# QCW_GDT_PCB.net
KiCad netlist of a schematic drawn in Altium Designer
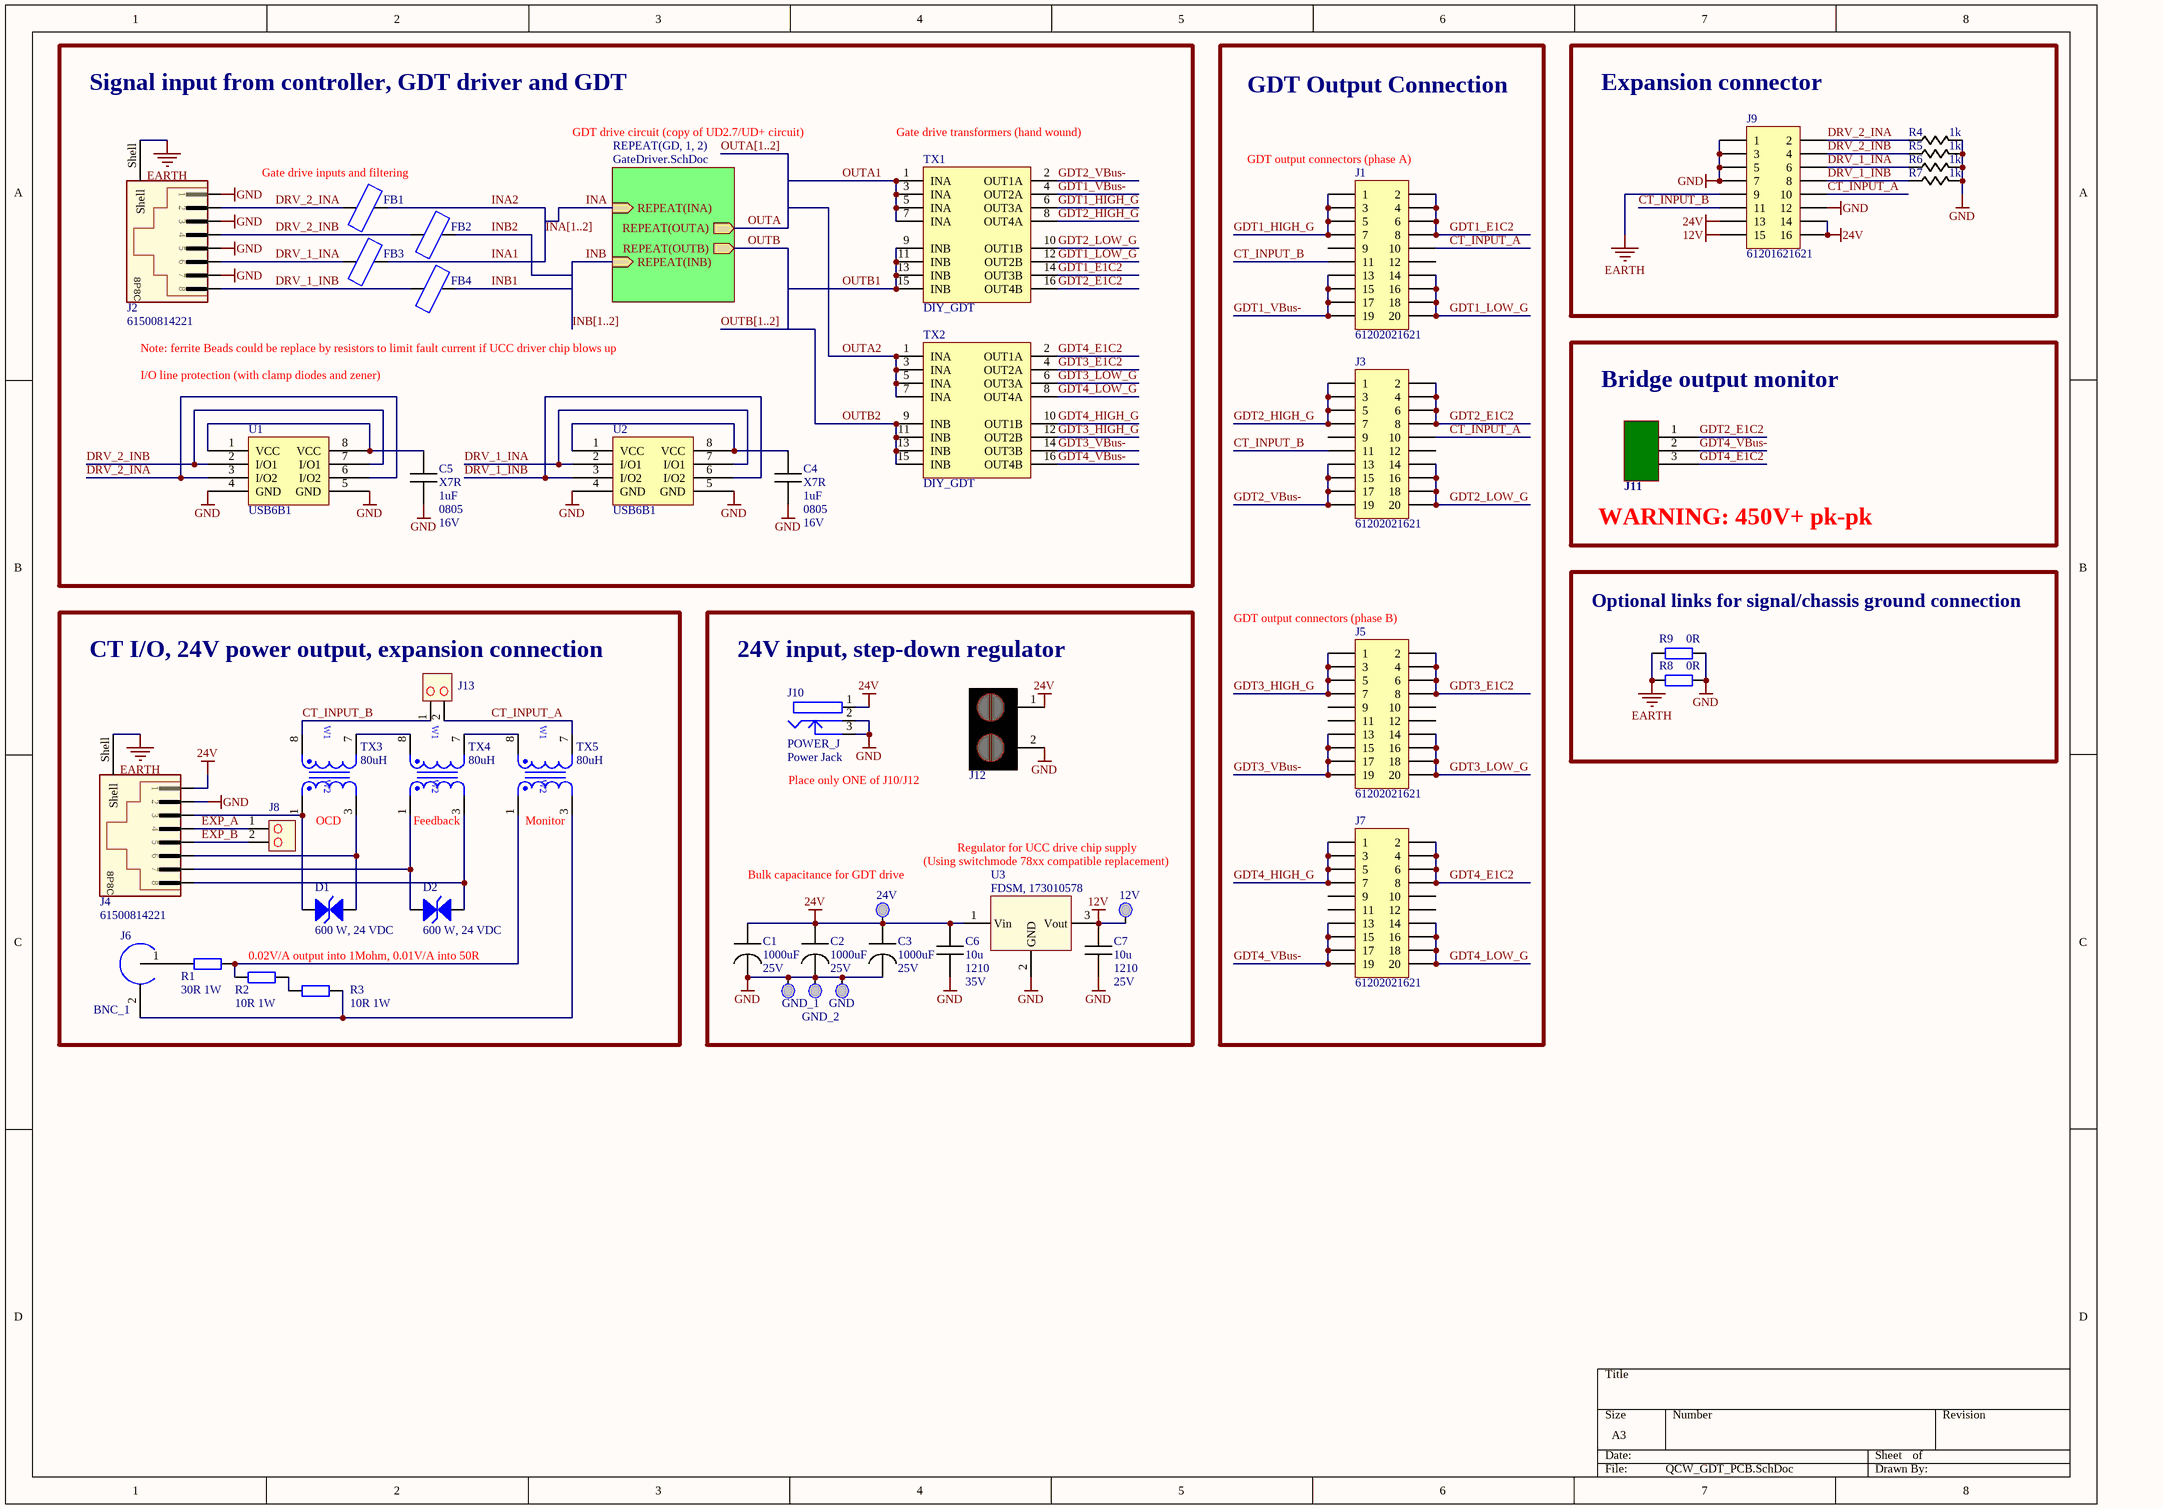
[diagram p0: QCW_GDT_PCB.SchDoc]

(export (version "E")
  (design (tool "Eeschema 10.0.6"))
  (components
    (comp (ref "12V")
      (value "Testpoint")
      (footprint "Keystone5004")
      (libsource (lib "TV_Altium_library") (part "Testpoint"))
    )
    (comp (ref "24V")
      (value "Testpoint")
      (footprint "Keystone5000")
      (libsource (lib "TV_Altium_library") (part "Testpoint"))
    )
    (comp (ref "C1")
      (value "EEU-FM1E102")
      (footprint "12.5mm lytic")
      (description "CAP ALUM 1000UF 20% 25V RADIAL")
      (fields
        (field (name "CAPACITANCE") "1000uF")
        (field (name "VOLTAGE") "25V")
        (field (name "MOUSER PART") "667-EEU-FM1E102")
        (field (name "DIGIKEY PART") "P12379-ND")
      )
      (libsource (lib "TV_Altium_library") (part "electrolytic capacitor"))
    )
    (comp (ref "C2")
      (value "EEU-FM1E102")
      (footprint "12.5mm lytic")
      (description "CAP ALUM 1000UF 20% 25V RADIAL")
      (fields
        (field (name "CAPACITANCE") "1000uF")
        (field (name "VOLTAGE") "25V")
        (field (name "MOUSER PART") "667-EEU-FM1E102")
        (field (name "DIGIKEY PART") "P12379-ND")
      )
      (libsource (lib "TV_Altium_library") (part "electrolytic capacitor"))
    )
    (comp (ref "C3")
      (value "EEU-FM1E102")
      (footprint "12.5mm lytic")
      (description "CAP ALUM 1000UF 20% 25V RADIAL")
      (fields
        (field (name "CAPACITANCE") "1000uF")
        (field (name "VOLTAGE") "25V")
        (field (name "MOUSER PART") "667-EEU-FM1E102")
        (field (name "DIGIKEY PART") "P12379-ND")
      )
      (libsource (lib "TV_Altium_library") (part "electrolytic capacitor"))
    )
    (comp (ref "C4")
      (value "CC0805KKX7R7BB105")
      (footprint "0805C")
      (description "CAP CER 1UF 16V X7R 0805")
      (fields
        (field (name "TOLERANCE") "10%")
        (field (name "MATERIAL") "X7R")
        (field (name "CAPACITANCE") "1uF")
        (field (name "PACKAGE") "0805")
        (field (name "VOLTAGE") "16V")
        (field (name "MOUSER PART") "603-CC805KKX7R7BB105")
      )
      (libsource (lib "UD2 CPLD") (part "Capacitor"))
    )
    (comp (ref "C5")
      (value "CC0805KKX7R7BB105")
      (footprint "0805C")
      (description "CAP CER 1UF 16V X7R 0805")
      (fields
        (field (name "TOLERANCE") "10%")
        (field (name "MATERIAL") "X7R")
        (field (name "CAPACITANCE") "1uF")
        (field (name "PACKAGE") "0805")
        (field (name "VOLTAGE") "16V")
        (field (name "MOUSER PART") "603-CC805KKX7R7BB105")
      )
      (libsource (lib "UD2 CPLD") (part "Capacitor"))
    )
    (comp (ref "C6")
      (value "885012209028")
      (footprint "1210C")
      (fields
        (field (name "CAPACITANCE") "10u")
        (field (name "PACKAGE") "1210")
        (field (name "VOLTAGE") "35V")
      )
      (libsource (lib "TV_Altium_library") (part "Capacitor"))
    )
    (comp (ref "C7")
      (value "885012209028")
      (footprint "1210C")
      (fields
        (field (name "CAPACITANCE") "10u")
        (field (name "PACKAGE") "1210")
        (field (name "VOLTAGE") "25V")
      )
      (libsource (lib "TV_Altium_library") (part "Capacitor"))
    )
    (comp (ref "D1")
      (value "600 W, 24 VDC")
      (footprint "DO-214AA_Bidirectional")
      (description "WE-TVSP Power TVS Diode, bidirectional, 600 W, 24 VDC")
      (fields
        (field (name "PARTNO") "824521241")
        (field (name "MANUFACTURER") "Wurth Elektronik")
        (field (name "CREATED BY") "Baojun Chen")
      )
      (libsource (lib "TV_Altium_library") (part "WE-TVSP DO-214AA, 824521241"))
    )
    (comp (ref "D2")
      (value "600 W, 24 VDC")
      (footprint "DO-214AA_Bidirectional")
      (description "WE-TVSP Power TVS Diode, bidirectional, 600 W, 24 VDC")
      (fields
        (field (name "PARTNO") "824521241")
        (field (name "MANUFACTURER") "Wurth Elektronik")
        (field (name "CREATED BY") "Baojun Chen")
      )
      (libsource (lib "TV_Altium_library") (part "WE-TVSP DO-214AA, 824521241"))
    )
    (comp (ref "FB1")
      (value "FerriteBead")
      (footprint "0805FB")
      (description "Ferrite Bead")
      (libsource (lib "TV_Altium_library") (part "FerriteBead"))
    )
    (comp (ref "FB2")
      (value "FerriteBead")
      (footprint "0805FB")
      (description "Ferrite Bead")
      (libsource (lib "TV_Altium_library") (part "FerriteBead"))
    )
    (comp (ref "FB3")
      (value "FerriteBead")
      (footprint "0805FB")
      (description "Ferrite Bead")
      (libsource (lib "TV_Altium_library") (part "FerriteBead"))
    )
    (comp (ref "FB4")
      (value "FerriteBead")
      (footprint "0805FB")
      (description "Ferrite Bead")
      (libsource (lib "TV_Altium_library") (part "FerriteBead"))
    )
    (comp (ref "GND")
      (value "Testpoint")
      (footprint "Keystone5001")
      (libsource (lib "TV_Altium_library") (part "Testpoint"))
    )
    (comp (ref "GND_1")
      (value "Testpoint")
      (footprint "Keystone5001")
      (libsource (lib "TV_Altium_library") (part "Testpoint"))
    )
    (comp (ref "GND_2")
      (value "Testpoint")
      (footprint "Keystone5001")
      (libsource (lib "TV_Altium_library") (part "Testpoint"))
    )
    (comp (ref "J1")
      (value "61202021621")
      (footprint "61202021621")
      (description "WR-BHD 2.54mm Male Box Header")
      (fields (field (name "MANUFACTURER") "Wurth Elektronik") (field (name "CREATED BY") "Baojun Chen"))
      (libsource (lib "TV_Altium_library") (part "61202021621"))
    )
    (comp (ref "J2")
      (value "61500814221")
      (footprint "61500814221")
      (description "WR-MJ Modular Jack Horizontal Shielded 8P8C Tab Down")
      (fields (field (name "PUBLISHER") "Wurth Elektronik"))
      (libsource (lib "TV_Altium_library") (part "61500814221"))
    )
    (comp (ref "J3")
      (value "61202021621")
      (footprint "61202021621")
      (description "WR-BHD 2.54mm Male Box Header")
      (fields (field (name "MANUFACTURER") "Wurth Elektronik") (field (name "CREATED BY") "Baojun Chen"))
      (libsource (lib "TV_Altium_library") (part "61202021621"))
    )
    (comp (ref "J4")
      (value "61500814221")
      (footprint "61500814221")
      (description "WR-MJ Modular Jack Horizontal Shielded 8P8C Tab Down")
      (fields (field (name "PUBLISHER") "Wurth Elektronik"))
      (libsource (lib "TV_Altium_library") (part "61500814221"))
    )
    (comp (ref "J5")
      (value "61202021621")
      (footprint "61202021621")
      (description "WR-BHD 2.54mm Male Box Header")
      (fields (field (name "MANUFACTURER") "Wurth Elektronik") (field (name "CREATED BY") "Baojun Chen"))
      (libsource (lib "TV_Altium_library") (part "61202021621"))
    )
    (comp (ref "J6")
      (value "BNC_1")
      (footprint "BNC_PLASTIC_ELBOW_SOCKET_WITH_MOUNTING_POSTS")
      (description "BNC Connector")
      (libsource (lib "TV_Altium_library") (part "BNC_1"))
    )
    (comp (ref "J7")
      (value "61202021621")
      (footprint "61202021621")
      (description "WR-BHD 2.54mm Male Box Header")
      (fields (field (name "MANUFACTURER") "Wurth Elektronik") (field (name "CREATED BY") "Baojun Chen"))
      (libsource (lib "TV_Altium_library") (part "61202021621"))
    )
    (comp (ref "J8")
      (value "22-23-2021")
      (footprint "22-23-2021")
      (description "Pin Header, 2 Position, Locking, .1 Centers")
      (libsource (lib "") (part "22-23-2021_1"))
    )
    (comp (ref "J9")
      (value "61201621621")
      (footprint "61201621621")
      (description "WR-BHD 2.54mm Male Box Header")
      (fields (field (name "MANUFACTURER") "Wurth Elektronik") (field (name "CREATED BY") "Baojun Chen"))
      (libsource (lib "TV_Altium_library") (part "61201621621"))
    )
    (comp (ref "J10")
      (value "POWER_J")
      (footprint "TV_Altium_Library:POWER_J_SLOT")
      (description "Low Voltage Power Supply Connector")
      (fields
        (field (name "PART_NUMBER") "OVC-CON-10108")
        (field (name "ALTIUM_VALUE") "Power Jack")
        (field (name "PUBLISHER") "Altium Limited")
      )
      (libsource (lib "TV_Altium_library") (part "POWER_J"))
    )
    (comp (ref "J11")
      (value "Header_3_right_angle_th_3.81mm")
      (footprint "691322310003")
      (description "3-way header")
      (libsource (lib "TV_Altium_library") (part "Header_3_right_angle_th_3.81mm"))
    )
    (comp (ref "J12")
      (value "Header_2_5.08mm_Screw_Black")
      (footprint "1776119-2")
      (description "2-way PCB connector")
      (libsource (lib "TV_Altium_library") (part "Header_2_5.08mm_Screw_Black"))
    )
    (comp (ref "J13")
      (value "22-23-2021")
      (footprint "22-23-2021")
      (description "Pin Header, 2 Position, Locking, .1 Centers")
      (libsource (lib "TV_Altium_library") (part "22-23-2021"))
    )
    (comp (ref "R1")
      (value "30R 1W")
      (footprint "RES_2512")
      (libsource (lib "TV_Altium_library") (part "Resistor"))
    )
    (comp (ref "R2")
      (value "10R 1W")
      (footprint "RES_2512")
      (libsource (lib "TV_Altium_library") (part "Resistor"))
    )
    (comp (ref "R3")
      (value "10R 1W")
      (footprint "RES_2512")
      (libsource (lib "TV_Altium_library") (part "Resistor"))
    )
    (comp (ref "R4")
      (value "RC0805FR-071KL")
      (footprint "0805R")
      (description "RES SMD 1K OHM 1% 1/8W 0805")
      (fields
        (field (name "POWER") "0.125W")
        (field (name "RESISTANCE") "1k")
        (field (name "TOLERANCE") "1%")
      )
      (libsource (lib "UD2 CPLD") (part "Resistor"))
    )
    (comp (ref "R5")
      (value "RC0805FR-071KL")
      (footprint "0805R")
      (description "RES SMD 1K OHM 1% 1/8W 0805")
      (fields
        (field (name "POWER") "0.125W")
        (field (name "RESISTANCE") "1k")
        (field (name "TOLERANCE") "1%")
      )
      (libsource (lib "UD2 CPLD") (part "Resistor"))
    )
    (comp (ref "R6")
      (value "RC0805FR-071KL")
      (footprint "0805R")
      (description "RES SMD 1K OHM 1% 1/8W 0805")
      (fields
        (field (name "POWER") "0.125W")
        (field (name "RESISTANCE") "1k")
        (field (name "TOLERANCE") "1%")
      )
      (libsource (lib "UD2 CPLD") (part "Resistor"))
    )
    (comp (ref "R7")
      (value "RC0805FR-071KL")
      (footprint "0805R")
      (description "RES SMD 1K OHM 1% 1/8W 0805")
      (fields
        (field (name "POWER") "0.125W")
        (field (name "RESISTANCE") "1k")
        (field (name "TOLERANCE") "1%")
      )
      (libsource (lib "UD2 CPLD") (part "Resistor"))
    )
    (comp (ref "R8") (value "0R") (footprint "1206R") (libsource (lib "TV_Altium_library") (part "Resistor")))
    (comp (ref "R9") (value "0R") (footprint "1206R") (libsource (lib "TV_Altium_library") (part "Resistor")))
    (comp (ref "TX1")
      (value "DIY_GDT")
      (footprint "GDT_DIY")
      (description "DIY Gate Drive TX on 36x22x14 toroid")
      (libsource (lib "TV_Altium_library") (part "GDT_DIY"))
    )
    (comp (ref "TX2")
      (value "DIY_GDT")
      (footprint "GDT_DIY")
      (description "DIY Gate Drive TX on 36x22x14 toroid")
      (libsource (lib "TV_Altium_library") (part "GDT_DIY"))
    )
    (comp (ref "TX3")
      (value "80uH")
      (footprint "WE-CST_EE5")
      (description "WE-CST Current Sense Transformer, EE5, 80uH")
      (fields (field (name "PARTNUMBER") "749251020") (field (name "PUBLISHER") "Wurth Elektronik"))
      (libsource (lib "TV_Altium_library") (part "WE-CST, 749251020"))
    )
    (comp (ref "TX4")
      (value "80uH")
      (footprint "WE-CST_EE5")
      (description "WE-CST Current Sense Transformer, EE5, 80uH")
      (fields (field (name "PARTNUMBER") "749251020") (field (name "PUBLISHER") "Wurth Elektronik"))
      (libsource (lib "TV_Altium_library") (part "WE-CST, 749251020"))
    )
    (comp (ref "TX5")
      (value "80uH")
      (footprint "WE-CST_EE5")
      (description "WE-CST Current Sense Transformer, EE5, 80uH")
      (fields (field (name "PARTNUMBER") "749251020") (field (name "PUBLISHER") "Wurth Elektronik"))
      (libsource (lib "TV_Altium_library") (part "WE-CST, 749251020"))
    )
    (comp (ref "U1")
      (value "USB6B1")
      (footprint "SOIC-8")
      (description "USB Data Line Protection")
      (libsource (lib "TV_Altium_library") (part "USB6B1"))
    )
    (comp (ref "U2")
      (value "USB6B1")
      (footprint "SOIC-8")
      (description "USB Data Line Protection")
      (libsource (lib "TV_Altium_library") (part "USB6B1"))
    )
    (comp (ref "U3")
      (value "FDSM, 173010578")
      (footprint "WE-FDSM_173010x78")
      (description "MagI³C-FDSM Fixed Step Down Regulator Module")
      (fields (field (name "PARTNUMBER") "173010578") (field (name "PUBLISHER") "Wurth Elektronik"))
      (libsource (lib "TV_Altium_library") (part "FDSM, 173010578"))
    )
  )
  (nets
    (net (code "1") (name "/CT_INPUT_A") (class "Default")
      (node (ref "J1") (pin "10") (pinfunction "10_10") (pintype "passive"))
      (node (ref "J13") (pin "2") (pinfunction "2_2") (pintype "passive"))
      (node (ref "J3") (pin "10") (pinfunction "10_10") (pintype "passive"))
      (node (ref "J9") (pin "10") (pinfunction "10_10") (pintype "passive"))
      (node (ref "TX5") (pin "7") (pinfunction "7_7") (pintype "passive"))
    )
    (net (code "2") (name "/CT_INPUT_B") (class "Default")
      (node (ref "J1") (pin "11") (pinfunction "11_11") (pintype "passive"))
      (node (ref "J13") (pin "1") (pinfunction "1_1") (pintype "passive"))
      (node (ref "J3") (pin "11") (pinfunction "11_11") (pintype "passive"))
      (node (ref "J9") (pin "11") (pinfunction "11_11") (pintype "passive"))
      (node (ref "TX3") (pin "8") (pinfunction "8_8") (pintype "passive"))
    )
    (net (code "3") (name "/DRV_1_INA") (class "Default")
      (node (ref "FB3") (pin "1") (pinfunction "1_1") (pintype "passive"))
      (node (ref "J2") (pin "6") (pinfunction "6_6") (pintype "passive"))
      (node (ref "J9") (pin "6") (pinfunction "6_6") (pintype "passive"))
      (node (ref "R6") (pin "2") (pinfunction "2_2") (pintype "passive"))
      (node (ref "U2") (pin "2") (pinfunction "I/O1_2") (pintype "passive"))
      (node (ref "U2") (pin "7") (pinfunction "I/O1_7") (pintype "passive"))
    )
    (net (code "4") (name "/DRV_1_INB") (class "Default")
      (node (ref "FB4") (pin "1") (pinfunction "1_1") (pintype "passive"))
      (node (ref "J2") (pin "8") (pinfunction "8_8") (pintype "passive"))
      (node (ref "J9") (pin "8") (pinfunction "8_8") (pintype "passive"))
      (node (ref "R7") (pin "2") (pinfunction "2_2") (pintype "passive"))
      (node (ref "U2") (pin "3") (pinfunction "I/O2_3") (pintype "passive"))
      (node (ref "U2") (pin "6") (pinfunction "I/O2_6") (pintype "passive"))
    )
    (net (code "5") (name "/DRV_2_INA") (class "Default")
      (node (ref "FB1") (pin "1") (pinfunction "1_1") (pintype "passive"))
      (node (ref "J2") (pin "2") (pinfunction "2_2") (pintype "passive"))
      (node (ref "J9") (pin "2") (pinfunction "2_2") (pintype "passive"))
      (node (ref "R4") (pin "2") (pinfunction "2_2") (pintype "passive"))
      (node (ref "U1") (pin "3") (pinfunction "I/O2_3") (pintype "passive"))
      (node (ref "U1") (pin "6") (pinfunction "I/O2_6") (pintype "passive"))
    )
    (net (code "6") (name "/DRV_2_INB") (class "Default")
      (node (ref "FB2") (pin "1") (pinfunction "1_1") (pintype "passive"))
      (node (ref "J2") (pin "4") (pinfunction "4_4") (pintype "passive"))
      (node (ref "J9") (pin "4") (pinfunction "4_4") (pintype "passive"))
      (node (ref "R5") (pin "2") (pinfunction "2_2") (pintype "passive"))
      (node (ref "U1") (pin "2") (pinfunction "I/O1_2") (pintype "passive"))
      (node (ref "U1") (pin "7") (pinfunction "I/O1_7") (pintype "passive"))
    )
    (net (code "7") (name "/EXP_A") (class "Default")
      (node (ref "J4") (pin "4") (pinfunction "4_4") (pintype "passive"))
      (node (ref "J8") (pin "1") (pinfunction "1_1") (pintype "passive"))
    )
    (net (code "8") (name "/EXP_B") (class "Default")
      (node (ref "J4") (pin "5") (pinfunction "5_5") (pintype "passive"))
      (node (ref "J8") (pin "2") (pinfunction "2_2") (pintype "passive"))
    )
    (net (code "9") (name "/GDT1_E1C2") (class "Default")
      (node (ref "J1") (pin "2") (pinfunction "2_2") (pintype "passive"))
      (node (ref "J1") (pin "4") (pinfunction "4_4") (pintype "passive"))
      (node (ref "J1") (pin "6") (pinfunction "6_6") (pintype "passive"))
      (node (ref "J1") (pin "8") (pinfunction "8_8") (pintype "passive"))
      (node (ref "TX1") (pin "14") (pinfunction "OUT3B_14") (pintype "passive"))
    )
    (net (code "10") (name "/GDT1_HIGH_G") (class "Default")
      (node (ref "J1") (pin "1") (pinfunction "1_1") (pintype "passive"))
      (node (ref "J1") (pin "3") (pinfunction "3_3") (pintype "passive"))
      (node (ref "J1") (pin "5") (pinfunction "5_5") (pintype "passive"))
      (node (ref "J1") (pin "7") (pinfunction "7_7") (pintype "passive"))
      (node (ref "TX1") (pin "6") (pinfunction "OUT3A_6") (pintype "passive"))
    )
    (net (code "11") (name "/GDT1_LOW_G") (class "Default")
      (node (ref "J1") (pin "14") (pinfunction "14_14") (pintype "passive"))
      (node (ref "J1") (pin "16") (pinfunction "16_16") (pintype "passive"))
      (node (ref "J1") (pin "18") (pinfunction "18_18") (pintype "passive"))
      (node (ref "J1") (pin "20") (pinfunction "20_20") (pintype "passive"))
      (node (ref "TX1") (pin "12") (pinfunction "OUT2B_12") (pintype "passive"))
    )
    (net (code "12") (name "/GDT1_VBus-") (class "Default")
      (node (ref "J1") (pin "13") (pinfunction "13_13") (pintype "passive"))
      (node (ref "J1") (pin "15") (pinfunction "15_15") (pintype "passive"))
      (node (ref "J1") (pin "17") (pinfunction "17_17") (pintype "passive"))
      (node (ref "J1") (pin "19") (pinfunction "19_19") (pintype "passive"))
      (node (ref "TX1") (pin "4") (pinfunction "OUT2A_4") (pintype "passive"))
    )
    (net (code "13") (name "/GDT2_E1C2") (class "Default")
      (node (ref "J11") (pin "1") (pintype "passive"))
      (node (ref "J3") (pin "2") (pinfunction "2_2") (pintype "passive"))
      (node (ref "J3") (pin "4") (pinfunction "4_4") (pintype "passive"))
      (node (ref "J3") (pin "6") (pinfunction "6_6") (pintype "passive"))
      (node (ref "J3") (pin "8") (pinfunction "8_8") (pintype "passive"))
      (node (ref "TX1") (pin "16") (pinfunction "OUT4B_16") (pintype "passive"))
    )
    (net (code "14") (name "/GDT2_HIGH_G") (class "Default")
      (node (ref "J3") (pin "1") (pinfunction "1_1") (pintype "passive"))
      (node (ref "J3") (pin "3") (pinfunction "3_3") (pintype "passive"))
      (node (ref "J3") (pin "5") (pinfunction "5_5") (pintype "passive"))
      (node (ref "J3") (pin "7") (pinfunction "7_7") (pintype "passive"))
      (node (ref "TX1") (pin "8") (pinfunction "OUT4A_8") (pintype "passive"))
    )
    (net (code "15") (name "/GDT2_LOW_G") (class "Default")
      (node (ref "J3") (pin "14") (pinfunction "14_14") (pintype "passive"))
      (node (ref "J3") (pin "16") (pinfunction "16_16") (pintype "passive"))
      (node (ref "J3") (pin "18") (pinfunction "18_18") (pintype "passive"))
      (node (ref "J3") (pin "20") (pinfunction "20_20") (pintype "passive"))
      (node (ref "TX1") (pin "10") (pinfunction "OUT1B_10") (pintype "passive"))
    )
    (net (code "16") (name "/GDT2_VBus-") (class "Default")
      (node (ref "J3") (pin "13") (pinfunction "13_13") (pintype "passive"))
      (node (ref "J3") (pin "15") (pinfunction "15_15") (pintype "passive"))
      (node (ref "J3") (pin "17") (pinfunction "17_17") (pintype "passive"))
      (node (ref "J3") (pin "19") (pinfunction "19_19") (pintype "passive"))
      (node (ref "TX1") (pin "2") (pinfunction "OUT1A_2") (pintype "passive"))
    )
    (net (code "17") (name "/GDT3_E1C2") (class "Default")
      (node (ref "J5") (pin "2") (pinfunction "2_2") (pintype "passive"))
      (node (ref "J5") (pin "4") (pinfunction "4_4") (pintype "passive"))
      (node (ref "J5") (pin "6") (pinfunction "6_6") (pintype "passive"))
      (node (ref "J5") (pin "8") (pinfunction "8_8") (pintype "passive"))
      (node (ref "TX2") (pin "4") (pinfunction "OUT2A_4") (pintype "passive"))
    )
    (net (code "18") (name "/GDT3_HIGH_G") (class "Default")
      (node (ref "J5") (pin "1") (pinfunction "1_1") (pintype "passive"))
      (node (ref "J5") (pin "3") (pinfunction "3_3") (pintype "passive"))
      (node (ref "J5") (pin "5") (pinfunction "5_5") (pintype "passive"))
      (node (ref "J5") (pin "7") (pinfunction "7_7") (pintype "passive"))
      (node (ref "TX2") (pin "12") (pinfunction "OUT2B_12") (pintype "passive"))
    )
    (net (code "19") (name "/GDT3_LOW_G") (class "Default")
      (node (ref "J5") (pin "14") (pinfunction "14_14") (pintype "passive"))
      (node (ref "J5") (pin "16") (pinfunction "16_16") (pintype "passive"))
      (node (ref "J5") (pin "18") (pinfunction "18_18") (pintype "passive"))
      (node (ref "J5") (pin "20") (pinfunction "20_20") (pintype "passive"))
      (node (ref "TX2") (pin "6") (pinfunction "OUT3A_6") (pintype "passive"))
    )
    (net (code "20") (name "/GDT3_VBus-") (class "Default")
      (node (ref "J5") (pin "13") (pinfunction "13_13") (pintype "passive"))
      (node (ref "J5") (pin "15") (pinfunction "15_15") (pintype "passive"))
      (node (ref "J5") (pin "17") (pinfunction "17_17") (pintype "passive"))
      (node (ref "J5") (pin "19") (pinfunction "19_19") (pintype "passive"))
      (node (ref "TX2") (pin "14") (pinfunction "OUT3B_14") (pintype "passive"))
    )
    (net (code "21") (name "/GDT4_E1C2") (class "Default")
      (node (ref "J11") (pin "3") (pintype "passive"))
      (node (ref "J7") (pin "2") (pinfunction "2_2") (pintype "passive"))
      (node (ref "J7") (pin "4") (pinfunction "4_4") (pintype "passive"))
      (node (ref "J7") (pin "6") (pinfunction "6_6") (pintype "passive"))
      (node (ref "J7") (pin "8") (pinfunction "8_8") (pintype "passive"))
      (node (ref "TX2") (pin "2") (pinfunction "OUT1A_2") (pintype "passive"))
    )
    (net (code "22") (name "/GDT4_HIGH_G") (class "Default")
      (node (ref "J7") (pin "1") (pinfunction "1_1") (pintype "passive"))
      (node (ref "J7") (pin "3") (pinfunction "3_3") (pintype "passive"))
      (node (ref "J7") (pin "5") (pinfunction "5_5") (pintype "passive"))
      (node (ref "J7") (pin "7") (pinfunction "7_7") (pintype "passive"))
      (node (ref "TX2") (pin "10") (pinfunction "OUT1B_10") (pintype "passive"))
    )
    (net (code "23") (name "/GDT4_LOW_G") (class "Default")
      (node (ref "J7") (pin "14") (pinfunction "14_14") (pintype "passive"))
      (node (ref "J7") (pin "16") (pinfunction "16_16") (pintype "passive"))
      (node (ref "J7") (pin "18") (pinfunction "18_18") (pintype "passive"))
      (node (ref "J7") (pin "20") (pinfunction "20_20") (pintype "passive"))
      (node (ref "TX2") (pin "8") (pinfunction "OUT4A_8") (pintype "passive"))
    )
    (net (code "24") (name "/GDT4_VBus-") (class "Default")
      (node (ref "J11") (pin "2") (pintype "passive"))
      (node (ref "J7") (pin "13") (pinfunction "13_13") (pintype "passive"))
      (node (ref "J7") (pin "15") (pinfunction "15_15") (pintype "passive"))
      (node (ref "J7") (pin "17") (pinfunction "17_17") (pintype "passive"))
      (node (ref "J7") (pin "19") (pinfunction "19_19") (pintype "passive"))
      (node (ref "TX2") (pin "16") (pinfunction "OUT4B_16") (pintype "passive"))
    )
    (net (code "26") (name "/INA1") (class "Default")
      (node (ref "FB3") (pin "2") (pinfunction "2_2") (pintype "passive"))
    )
    (net (code "27") (name "/INA2") (class "Default")
      (node (ref "FB1") (pin "2") (pinfunction "2_2") (pintype "passive"))
    )
    (net (code "30") (name "/INB1") (class "Default")
      (node (ref "FB4") (pin "2") (pinfunction "2_2") (pintype "passive"))
    )
    (net (code "31") (name "/INB2") (class "Default")
      (node (ref "FB2") (pin "2") (pinfunction "2_2") (pintype "passive"))
    )
    (net (code "34") (name "/OUTA1") (class "Default")
      (node (ref "TX1") (pin "1") (pinfunction "INA_1") (pintype "passive"))
      (node (ref "TX1") (pin "3") (pinfunction "INA_3") (pintype "passive"))
      (node (ref "TX1") (pin "5") (pinfunction "INA_5") (pintype "passive"))
      (node (ref "TX1") (pin "7") (pinfunction "INA_7") (pintype "passive"))
    )
    (net (code "35") (name "/OUTA2") (class "Default")
      (node (ref "TX2") (pin "1") (pinfunction "INA_1") (pintype "passive"))
      (node (ref "TX2") (pin "3") (pinfunction "INA_3") (pintype "passive"))
      (node (ref "TX2") (pin "5") (pinfunction "INA_5") (pintype "passive"))
      (node (ref "TX2") (pin "7") (pinfunction "INA_7") (pintype "passive"))
    )
    (net (code "38") (name "/OUTB1") (class "Default")
      (node (ref "TX1") (pin "11") (pinfunction "INB_11") (pintype "passive"))
      (node (ref "TX1") (pin "13") (pinfunction "INB_13") (pintype "passive"))
      (node (ref "TX1") (pin "15") (pinfunction "INB_15") (pintype "passive"))
      (node (ref "TX1") (pin "9") (pinfunction "INB_9") (pintype "passive"))
    )
    (net (code "39") (name "/OUTB2") (class "Default")
      (node (ref "TX2") (pin "11") (pinfunction "INB_11") (pintype "passive"))
      (node (ref "TX2") (pin "13") (pinfunction "INB_13") (pintype "passive"))
      (node (ref "TX2") (pin "15") (pinfunction "INB_15") (pintype "passive"))
      (node (ref "TX2") (pin "9") (pinfunction "INB_9") (pintype "passive"))
    )
    (net (code "41") (name "12V") (class "Default")
      (node (ref "12V") (pin "1") (pinfunction "1_1") (pintype "passive"))
      (node (ref "C7") (pin "1") (pinfunction "1_1") (pintype "passive"))
      (node (ref "J9") (pin "15") (pinfunction "15_15") (pintype "passive"))
      (node (ref "U3") (pin "3") (pinfunction "Vout_3") (pintype "passive"))
    )
    (net (code "42") (name "24V") (class "Default")
      (node (ref "24V") (pin "1") (pinfunction "1_1") (pintype "passive"))
      (node (ref "C1") (pin "1") (pinfunction "1_1") (pintype "passive"))
      (node (ref "C2") (pin "1") (pinfunction "1_1") (pintype "passive"))
      (node (ref "C3") (pin "1") (pinfunction "1_1") (pintype "passive"))
      (node (ref "C6") (pin "1") (pinfunction "1_1") (pintype "passive"))
      (node (ref "J10") (pin "1") (pinfunction "1_1") (pintype "power_in"))
      (node (ref "J12") (pin "1") (pinfunction "1_1") (pintype "passive"))
      (node (ref "J4") (pin "1") (pinfunction "1_1") (pintype "passive"))
      (node (ref "J9") (pin "13") (pinfunction "13_13") (pintype "passive"))
      (node (ref "J9") (pin "14") (pinfunction "14_14") (pintype "passive"))
      (node (ref "J9") (pin "16") (pinfunction "16_16") (pintype "passive"))
      (node (ref "U3") (pin "1") (pinfunction "Vin_1") (pintype "passive"))
    )
    (net (code "43") (name "EARTH") (class "Default")
      (node (ref "J2") (pin "Shell") (pinfunction "Shell_Shell") (pintype "passive"))
      (node (ref "J4") (pin "Shell") (pinfunction "Shell_Shell") (pintype "passive"))
      (node (ref "J9") (pin "9") (pinfunction "9_9") (pintype "passive"))
      (node (ref "R8") (pin "2") (pinfunction "2_2") (pintype "passive"))
      (node (ref "R9") (pin "2") (pinfunction "2_2") (pintype "passive"))
    )
    (net (code "44") (name "GND") (class "Default")
      (node (ref "C1") (pin "2") (pinfunction "2_2") (pintype "passive"))
      (node (ref "C2") (pin "2") (pinfunction "2_2") (pintype "passive"))
      (node (ref "C3") (pin "2") (pinfunction "2_2") (pintype "passive"))
      (node (ref "C4") (pin "1") (pinfunction "1_1") (pintype "passive"))
      (node (ref "C5") (pin "1") (pinfunction "1_1") (pintype "passive"))
      (node (ref "C6") (pin "2") (pinfunction "2_2") (pintype "passive"))
      (node (ref "C7") (pin "2") (pinfunction "2_2") (pintype "passive"))
      (node (ref "GND") (pin "1") (pinfunction "1_1") (pintype "passive"))
      (node (ref "GND_1") (pin "1") (pinfunction "1_1") (pintype "passive"))
      (node (ref "GND_2") (pin "1") (pinfunction "1_1") (pintype "passive"))
      (node (ref "J10") (pin "2") (pinfunction "2_2") (pintype "power_in"))
      (node (ref "J10") (pin "3") (pinfunction "3_3") (pintype "power_in"))
      (node (ref "J12") (pin "2") (pinfunction "2_2") (pintype "passive"))
      (node (ref "J2") (pin "1") (pinfunction "1_1") (pintype "passive"))
      (node (ref "J2") (pin "3") (pinfunction "3_3") (pintype "passive"))
      (node (ref "J2") (pin "5") (pinfunction "5_5") (pintype "passive"))
      (node (ref "J2") (pin "7") (pinfunction "7_7") (pintype "passive"))
      (node (ref "J4") (pin "2") (pinfunction "2_2") (pintype "passive"))
      (node (ref "J9") (pin "1") (pinfunction "1_1") (pintype "passive"))
      (node (ref "J9") (pin "12") (pinfunction "12_12") (pintype "passive"))
      (node (ref "J9") (pin "3") (pinfunction "3_3") (pintype "passive"))
      (node (ref "J9") (pin "5") (pinfunction "5_5") (pintype "passive"))
      (node (ref "J9") (pin "7") (pinfunction "7_7") (pintype "passive"))
      (node (ref "R4") (pin "1") (pinfunction "1_1") (pintype "passive"))
      (node (ref "R5") (pin "1") (pinfunction "1_1") (pintype "passive"))
      (node (ref "R6") (pin "1") (pinfunction "1_1") (pintype "passive"))
      (node (ref "R7") (pin "1") (pinfunction "1_1") (pintype "passive"))
      (node (ref "R8") (pin "1") (pinfunction "1_1") (pintype "passive"))
      (node (ref "R9") (pin "1") (pinfunction "1_1") (pintype "passive"))
      (node (ref "U1") (pin "4") (pinfunction "GND_4") (pintype "passive"))
      (node (ref "U1") (pin "5") (pinfunction "GND_5") (pintype "passive"))
      (node (ref "U2") (pin "4") (pinfunction "GND_4") (pintype "passive"))
      (node (ref "U2") (pin "5") (pinfunction "GND_5") (pintype "passive"))
      (node (ref "U3") (pin "2") (pinfunction "GND_2") (pintype "passive"))
    )
    (net (code "45") (name "Net-(C4-Pad2)") (class "Default")
      (node (ref "C4") (pin "2") (pinfunction "2_2") (pintype "passive"))
      (node (ref "U2") (pin "1") (pinfunction "VCC_1") (pintype "passive"))
      (node (ref "U2") (pin "8") (pinfunction "VCC_8") (pintype "passive"))
    )
    (net (code "46") (name "Net-(C5-Pad2)") (class "Default")
      (node (ref "C5") (pin "2") (pinfunction "2_2") (pintype "passive"))
      (node (ref "U1") (pin "1") (pinfunction "VCC_1") (pintype "passive"))
      (node (ref "U1") (pin "8") (pinfunction "VCC_8") (pintype "passive"))
    )
    (net (code "47") (name "Net-(D1-Pad1)") (class "Default")
      (node (ref "D1") (pin "1") (pinfunction "1_1") (pintype "passive"))
      (node (ref "J4") (pin "3") (pinfunction "3_3") (pintype "passive"))
      (node (ref "TX3") (pin "1") (pinfunction "1_1") (pintype "passive"))
    )
    (net (code "48") (name "Net-(D1-Pad2)") (class "Default")
      (node (ref "D1") (pin "2") (pinfunction "2_2") (pintype "passive"))
      (node (ref "J4") (pin "6") (pinfunction "6_6") (pintype "passive"))
      (node (ref "TX3") (pin "3") (pinfunction "3_3") (pintype "passive"))
    )
    (net (code "49") (name "Net-(D2-Pad1)") (class "Default")
      (node (ref "D2") (pin "1") (pinfunction "1_1") (pintype "passive"))
      (node (ref "J4") (pin "7") (pinfunction "7_7") (pintype "passive"))
      (node (ref "TX4") (pin "1") (pinfunction "1_1") (pintype "passive"))
    )
    (net (code "50") (name "Net-(D2-Pad2)") (class "Default")
      (node (ref "D2") (pin "2") (pinfunction "2_2") (pintype "passive"))
      (node (ref "J4") (pin "8") (pinfunction "8_8") (pintype "passive"))
      (node (ref "TX4") (pin "3") (pinfunction "3_3") (pintype "passive"))
    )
    (net (code "51") (name "Net-(J6-Centre)") (class "Default")
      (node (ref "J6") (pin "1") (pinfunction "Centre_1") (pintype "passive"))
      (node (ref "R1") (pin "2") (pinfunction "2_2") (pintype "passive"))
    )
    (net (code "52") (name "Net-(J6-Shield)") (class "Default")
      (node (ref "J6") (pin "2") (pinfunction "Shield_2") (pintype "passive"))
      (node (ref "R3") (pin "1") (pinfunction "1_1") (pintype "passive"))
      (node (ref "TX5") (pin "3") (pinfunction "3_3") (pintype "passive"))
    )
    (net (code "53") (name "Net-(R1-Pad1)") (class "Default")
      (node (ref "R1") (pin "1") (pinfunction "1_1") (pintype "passive"))
      (node (ref "R2") (pin "2") (pinfunction "2_2") (pintype "passive"))
      (node (ref "TX5") (pin "1") (pinfunction "1_1") (pintype "passive"))
    )
    (net (code "54") (name "Net-(R2-Pad1)") (class "Default")
      (node (ref "R2") (pin "1") (pinfunction "1_1") (pintype "passive"))
      (node (ref "R3") (pin "2") (pinfunction "2_2") (pintype "passive"))
    )
    (net (code "55") (name "Net-(TX3-Pad7)") (class "Default")
      (node (ref "TX3") (pin "7") (pinfunction "7_7") (pintype "passive"))
      (node (ref "TX4") (pin "8") (pinfunction "8_8") (pintype "passive"))
    )
    (net (code "56") (name "Net-(TX4-Pad7)") (class "Default")
      (node (ref "TX4") (pin "7") (pinfunction "7_7") (pintype "passive"))
      (node (ref "TX5") (pin "8") (pinfunction "8_8") (pintype "passive"))
    )
    (net (code "57") (name "unconnected-(J1-Pad9)") (class "Default")
      (node (ref "J1") (pin "9") (pinfunction "9_9") (pintype "passive"))
    )
    (net (code "58") (name "unconnected-(J1-Pad12)") (class "Default")
      (node (ref "J1") (pin "12") (pinfunction "12_12") (pintype "passive"))
    )
    (net (code "59") (name "unconnected-(J3-Pad9)") (class "Default")
      (node (ref "J3") (pin "9") (pinfunction "9_9") (pintype "passive"))
    )
    (net (code "60") (name "unconnected-(J3-Pad12)") (class "Default")
      (node (ref "J3") (pin "12") (pinfunction "12_12") (pintype "passive"))
    )
    (net (code "61") (name "unconnected-(J5-Pad9)") (class "Default")
      (node (ref "J5") (pin "9") (pinfunction "9_9") (pintype "passive"))
    )
    (net (code "62") (name "unconnected-(J5-Pad10)") (class "Default")
      (node (ref "J5") (pin "10") (pinfunction "10_10") (pintype "passive"))
    )
    (net (code "63") (name "unconnected-(J5-Pad11)") (class "Default")
      (node (ref "J5") (pin "11") (pinfunction "11_11") (pintype "passive"))
    )
    (net (code "64") (name "unconnected-(J5-Pad12)") (class "Default")
      (node (ref "J5") (pin "12") (pinfunction "12_12") (pintype "passive"))
    )
    (net (code "65") (name "unconnected-(J7-Pad9)") (class "Default")
      (node (ref "J7") (pin "9") (pinfunction "9_9") (pintype "passive"))
    )
    (net (code "66") (name "unconnected-(J7-Pad10)") (class "Default")
      (node (ref "J7") (pin "10") (pinfunction "10_10") (pintype "passive"))
    )
    (net (code "67") (name "unconnected-(J7-Pad11)") (class "Default")
      (node (ref "J7") (pin "11") (pinfunction "11_11") (pintype "passive"))
    )
    (net (code "68") (name "unconnected-(J7-Pad12)") (class "Default")
      (node (ref "J7") (pin "12") (pinfunction "12_12") (pintype "passive"))
    )
  )
)
